# mechanics.net
KiCad netlist of a schematic drawn in Altium Designer
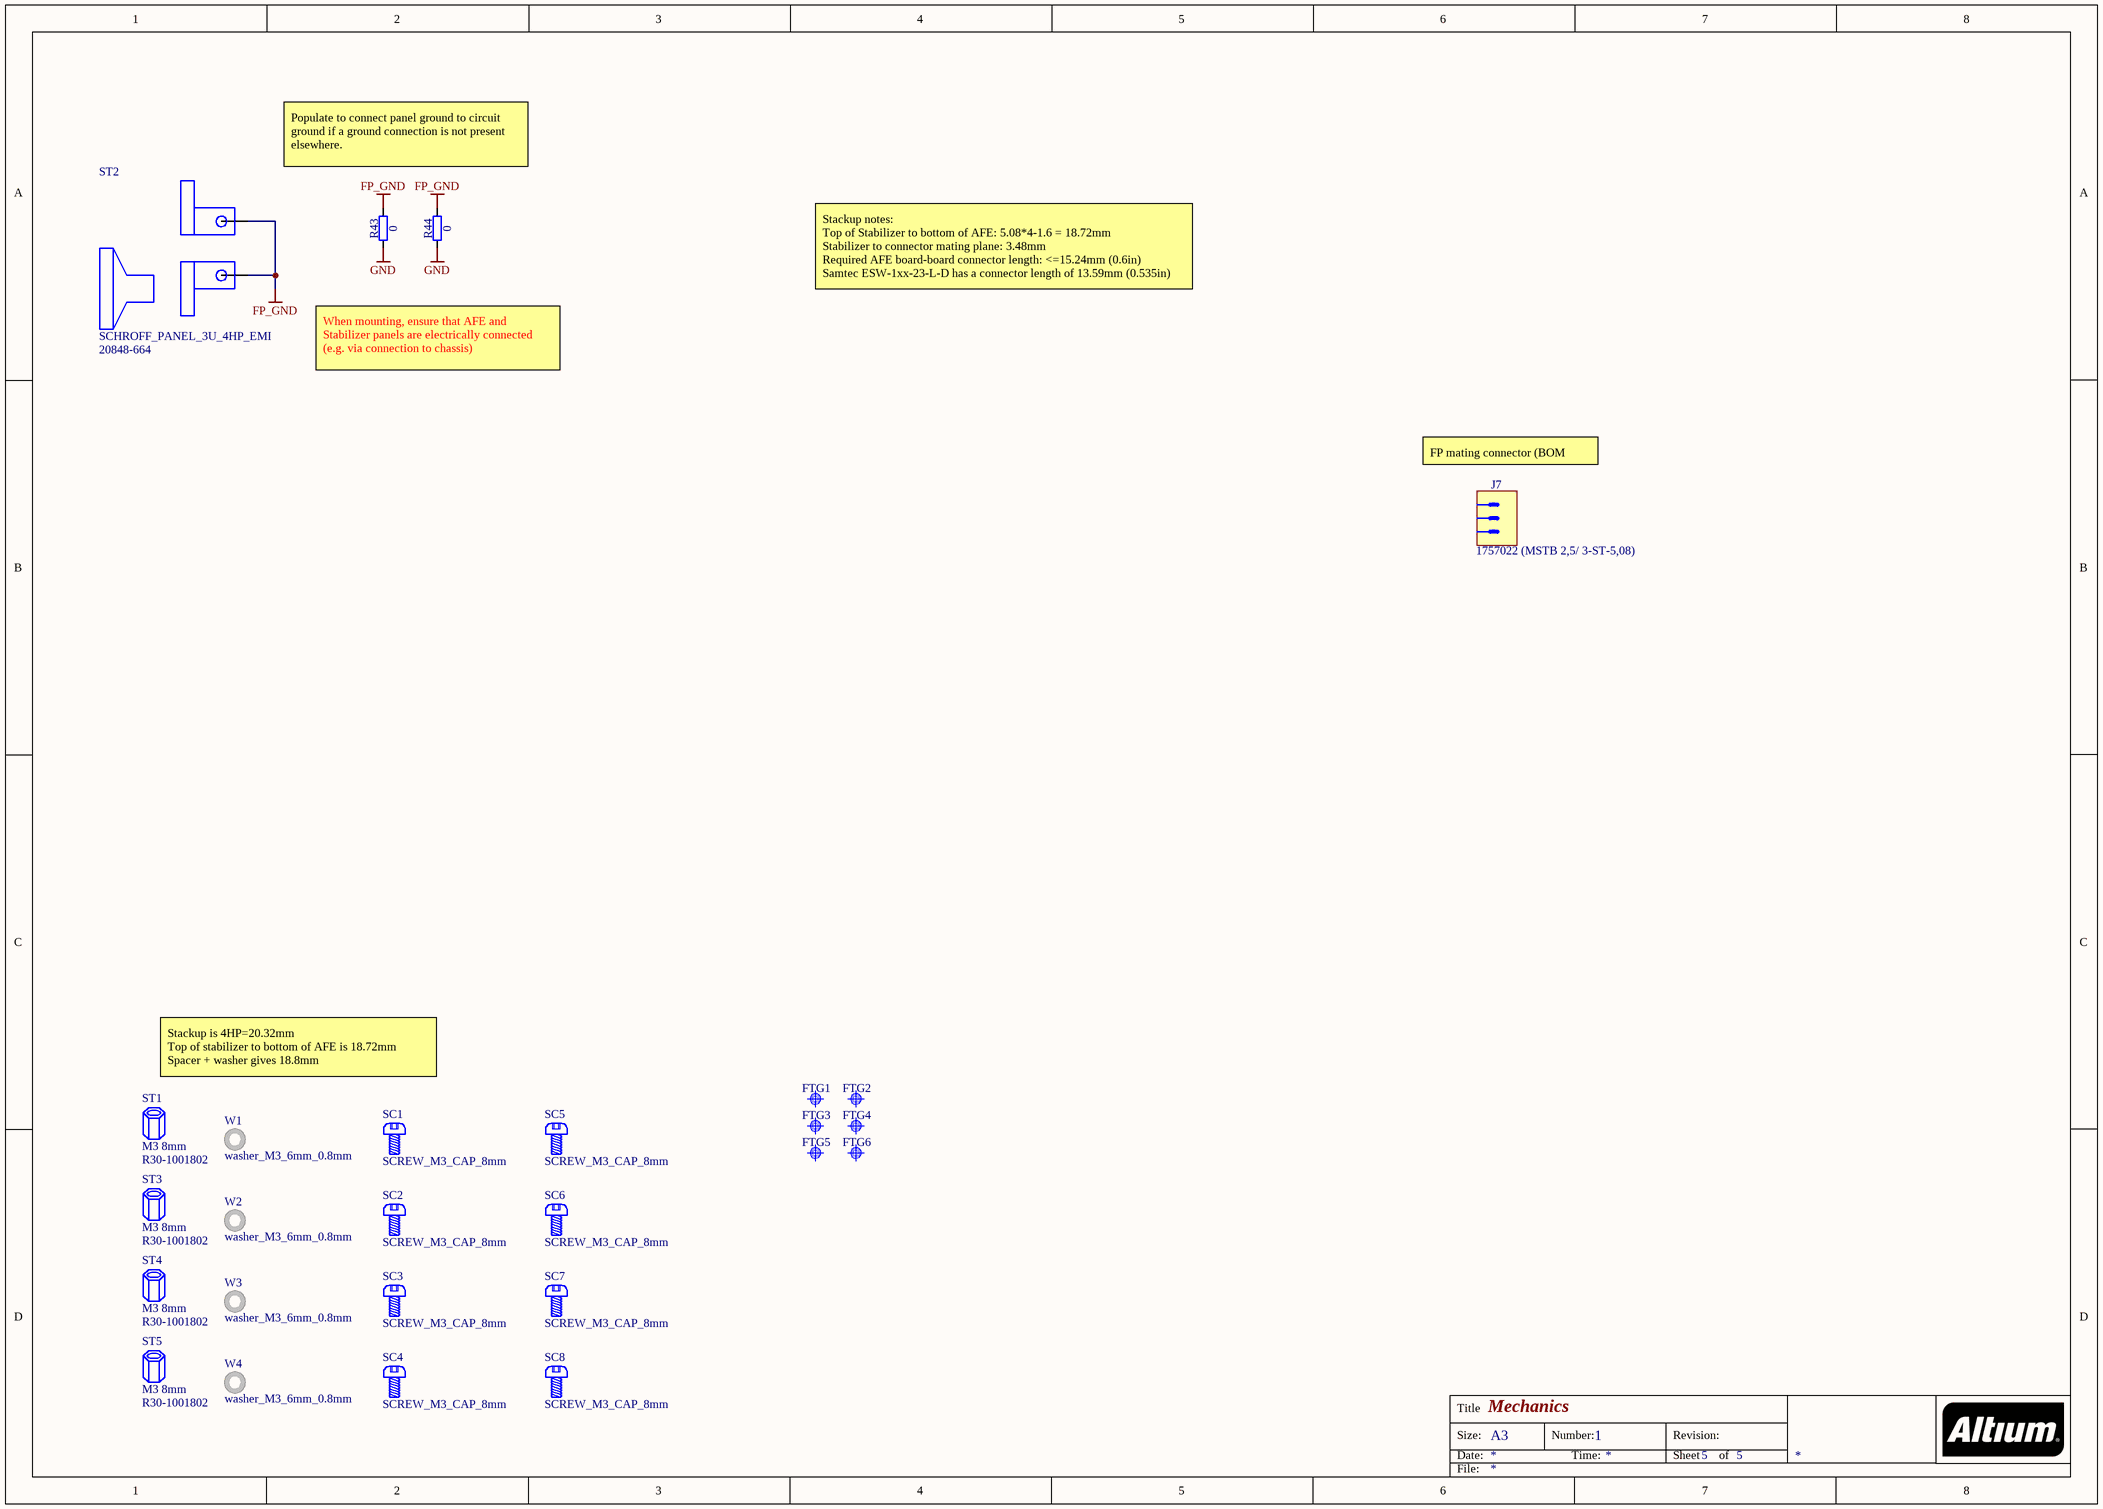
[diagram p0: mechanics.SchDoc]

(export (version "E")
  (design (tool "Eeschema 10.0.6"))
  (components
    (comp (ref "FTG1")
      (value "Use only in PCB")
      (footprint "FIDUCIAL_TOP_C100-200")
      (description "Fiducial Target")
      (fields (field (name "PART NUMBER") "FIDUCIAL_TARGET_C100-200") (field (name "AUTHOR") "CERN DEM JLC"))
      (libsource (lib "Eletro-mechanical") (part "Fiducial Target"))
    )
    (comp (ref "FTG2")
      (value "Use only in PCB")
      (footprint "FIDUCIAL_TOP_C100-200")
      (description "Fiducial Target")
      (fields (field (name "PART NUMBER") "FIDUCIAL_TARGET_C100-200") (field (name "AUTHOR") "CERN DEM JLC"))
      (libsource (lib "Eletro-mechanical") (part "Fiducial Target"))
    )
    (comp (ref "FTG3")
      (value "Use only in PCB")
      (footprint "FIDUCIAL_TOP_C100-200")
      (description "Fiducial Target")
      (fields (field (name "PART NUMBER") "FIDUCIAL_TARGET_C100-200") (field (name "AUTHOR") "CERN DEM JLC"))
      (libsource (lib "Eletro-mechanical") (part "Fiducial Target"))
    )
    (comp (ref "FTG4")
      (value "Use only in PCB")
      (footprint "FIDUCIAL_TOP_C100-200")
      (description "Fiducial Target")
      (fields (field (name "PART NUMBER") "FIDUCIAL_TARGET_C100-200") (field (name "AUTHOR") "CERN DEM JLC"))
      (libsource (lib "Eletro-mechanical") (part "Fiducial Target"))
    )
    (comp (ref "FTG5")
      (value "Use only in PCB")
      (footprint "FIDUCIAL_TOP_C100-200")
      (description "Fiducial Target")
      (fields (field (name "PART NUMBER") "FIDUCIAL_TARGET_C100-200") (field (name "AUTHOR") "CERN DEM JLC"))
      (libsource (lib "Eletro-mechanical") (part "Fiducial Target"))
    )
    (comp (ref "FTG6")
      (value "Use only in PCB")
      (footprint "FIDUCIAL_TOP_C100-200")
      (description "Fiducial Target")
      (fields (field (name "PART NUMBER") "FIDUCIAL_TARGET_C100-200") (field (name "AUTHOR") "CERN DEM JLC"))
      (libsource (lib "Eletro-mechanical") (part "Fiducial Target"))
    )
    (comp (ref "J7")
      (value "~")
      (footprint "connectors:PHOENIX_1757022")
      (description "Phoenix Contact 5.08mm pitch terminal plug, 3 ways")
      (fields
        (field (name "MANUFACTURER") "Phoenix Contact")
        (field (name "MANUFACTURER PART NUMBER") "1757022 (MSTB 2,5/ 3-ST-5,08)")
      )
      (libsource (lib "connectors") (part "PHOENIX_1757022"))
    )
    (comp (ref "R43")
      (value "0")
      (footprint "RESC1608X55N")
      (description "Resistor")
      (fields
        (field (name "PART NUMBER") "R0603_0R_JUMPER")
        (field (name "MANUFACTURER") "GENERIC")
        (field (name "AUTHOR") "CERN DEM JLC")
      )
      (libsource (lib "Resistors") (part "Resistor"))
    )
    (comp (ref "R44")
      (value "0")
      (footprint "RESC1608X55N")
      (description "Resistor")
      (fields
        (field (name "PART NUMBER") "R0603_0R_JUMPER")
        (field (name "MANUFACTURER") "GENERIC")
        (field (name "AUTHOR") "CERN DEM JLC")
      )
      (libsource (lib "Resistors") (part "Resistor"))
    )
    (comp (ref "SC1")
      (value "SCREW_M3_CAP_8mm")
      (footprint "mechanical:SCREW_M3_CAP_8mm")
      (description "M3 x 8mm cap head screw")
      (fields
        (field (name "MANUFACTURER") "Accu Limited")
        (field (name "MANUFACTURER PART NUMBER") "SSCF-M3-8-12.9-Z")
      )
      (libsource (lib "mechanical") (part "SCREW_M3_CAP_8mm"))
    )
    (comp (ref "SC2")
      (value "SCREW_M3_CAP_8mm")
      (footprint "mechanical:SCREW_M3_CAP_8mm")
      (description "M3 x 8mm cap head screw")
      (fields
        (field (name "MANUFACTURER") "Accu Limited")
        (field (name "MANUFACTURER PART NUMBER") "SSCF-M3-8-12.9-Z")
      )
      (libsource (lib "mechanical") (part "SCREW_M3_CAP_8mm"))
    )
    (comp (ref "SC3")
      (value "SCREW_M3_CAP_8mm")
      (footprint "mechanical:SCREW_M3_CAP_8mm")
      (description "M3 x 8mm cap head screw")
      (fields
        (field (name "MANUFACTURER") "Accu Limited")
        (field (name "MANUFACTURER PART NUMBER") "SSCF-M3-8-12.9-Z")
      )
      (libsource (lib "mechanical") (part "SCREW_M3_CAP_8mm"))
    )
    (comp (ref "SC4")
      (value "SCREW_M3_CAP_8mm")
      (footprint "mechanical:SCREW_M3_CAP_8mm")
      (description "M3 x 8mm cap head screw")
      (fields
        (field (name "MANUFACTURER") "Accu Limited")
        (field (name "MANUFACTURER PART NUMBER") "SSCF-M3-8-12.9-Z")
      )
      (libsource (lib "mechanical") (part "SCREW_M3_CAP_8mm"))
    )
    (comp (ref "SC5")
      (value "SCREW_M3_CAP_8mm")
      (footprint "mechanical:SCREW_M3_CAP_8mm")
      (description "M3 x 8mm cap head screw")
      (fields
        (field (name "MANUFACTURER") "Accu Limited")
        (field (name "MANUFACTURER PART NUMBER") "SSCF-M3-8-12.9-Z")
      )
      (libsource (lib "mechanical") (part "SCREW_M3_CAP_8mm"))
    )
    (comp (ref "SC6")
      (value "SCREW_M3_CAP_8mm")
      (footprint "mechanical:SCREW_M3_CAP_8mm")
      (description "M3 x 8mm cap head screw")
      (fields
        (field (name "MANUFACTURER") "Accu Limited")
        (field (name "MANUFACTURER PART NUMBER") "SSCF-M3-8-12.9-Z")
      )
      (libsource (lib "mechanical") (part "SCREW_M3_CAP_8mm"))
    )
    (comp (ref "SC7")
      (value "SCREW_M3_CAP_8mm")
      (footprint "mechanical:SCREW_M3_CAP_8mm")
      (description "M3 x 8mm cap head screw")
      (fields
        (field (name "MANUFACTURER") "Accu Limited")
        (field (name "MANUFACTURER PART NUMBER") "SSCF-M3-8-12.9-Z")
      )
      (libsource (lib "mechanical") (part "SCREW_M3_CAP_8mm"))
    )
    (comp (ref "SC8")
      (value "SCREW_M3_CAP_8mm")
      (footprint "mechanical:SCREW_M3_CAP_8mm")
      (description "M3 x 8mm cap head screw")
      (fields
        (field (name "MANUFACTURER") "Accu Limited")
        (field (name "MANUFACTURER PART NUMBER") "SSCF-M3-8-12.9-Z")
      )
      (libsource (lib "mechanical") (part "SCREW_M3_CAP_8mm"))
    )
    (comp (ref "ST1")
      (value "M3 8mm")
      (footprint "mechanical:R30-1001802")
      (description "M3.0x18 standoff")
      (fields (field (name "MANUFACTURER") "Harwin") (field (name "MANUFACTURER PART NUMBER") "R30-1001802"))
      (libsource (lib "mechanical") (part "STANDOFF_HARWIN_R30_1001802"))
    )
    (comp (ref "ST2")
      (value "SCHROFF_PANEL_3U_4HP_EMI")
      (footprint "mechanical:SCHROFF_PANEL_3HP_4U")
      (description "Schroff 3HP 4U EUROCARD Panel with EMI gaskets kit")
      (fields (field (name "MANUFACTURER") "Schroff") (field (name "MANUFACTURER PART NUMBER") "20848-664"))
      (libsource (lib "mechanical") (part "SCHROFF_PANEL_3U_4HP_EMI"))
    )
    (comp (ref "ST3")
      (value "M3 8mm")
      (footprint "mechanical:R30-1001802")
      (description "M3.0x18 standoff")
      (fields (field (name "MANUFACTURER") "Harwin") (field (name "MANUFACTURER PART NUMBER") "R30-1001802"))
      (libsource (lib "mechanical") (part "STANDOFF_HARWIN_R30_1001802"))
    )
    (comp (ref "ST4")
      (value "M3 8mm")
      (footprint "mechanical:R30-1001802")
      (description "M3.0x18 standoff")
      (fields (field (name "MANUFACTURER") "Harwin") (field (name "MANUFACTURER PART NUMBER") "R30-1001802"))
      (libsource (lib "mechanical") (part "STANDOFF_HARWIN_R30_1001802"))
    )
    (comp (ref "ST5")
      (value "M3 8mm")
      (footprint "mechanical:R30-1001802")
      (description "M3.0x18 standoff")
      (fields (field (name "MANUFACTURER") "Harwin") (field (name "MANUFACTURER PART NUMBER") "R30-1001802"))
      (libsource (lib "mechanical") (part "STANDOFF_HARWIN_R30_1001802"))
    )
    (comp (ref "W1")
      (value "washer_M3_6mm_0.8mm")
      (footprint "mechanical:washer_M3_6mm_0.8mm")
      (description "M3 Washer:\r\nID: 3.2mm\r\nOD: 6mm\r\nThickness 0.8mm")
      (fields
        (field (name "MANUFACTURER") "Accu Limited")
        (field (name "MANUFACTURER PART NUMBER") "HAFZ-M3-A4")
      )
      (libsource (lib "mechanical") (part "washer_M3_6mm_0.8mm"))
    )
    (comp (ref "W2")
      (value "washer_M3_6mm_0.8mm")
      (footprint "mechanical:washer_M3_6mm_0.8mm")
      (description "M3 Washer:\r\nID: 3.2mm\r\nOD: 6mm\r\nThickness 0.8mm")
      (fields
        (field (name "MANUFACTURER") "Accu Limited")
        (field (name "MANUFACTURER PART NUMBER") "HAFZ-M3-A4")
      )
      (libsource (lib "mechanical") (part "washer_M3_6mm_0.8mm"))
    )
    (comp (ref "W3")
      (value "washer_M3_6mm_0.8mm")
      (footprint "mechanical:washer_M3_6mm_0.8mm")
      (description "M3 Washer:\r\nID: 3.2mm\r\nOD: 6mm\r\nThickness 0.8mm")
      (fields
        (field (name "MANUFACTURER") "Accu Limited")
        (field (name "MANUFACTURER PART NUMBER") "HAFZ-M3-A4")
      )
      (libsource (lib "mechanical") (part "washer_M3_6mm_0.8mm"))
    )
    (comp (ref "W4")
      (value "washer_M3_6mm_0.8mm")
      (footprint "mechanical:washer_M3_6mm_0.8mm")
      (description "M3 Washer:\r\nID: 3.2mm\r\nOD: 6mm\r\nThickness 0.8mm")
      (fields
        (field (name "MANUFACTURER") "Accu Limited")
        (field (name "MANUFACTURER PART NUMBER") "HAFZ-M3-A4")
      )
      (libsource (lib "mechanical") (part "washer_M3_6mm_0.8mm"))
    )
  )
  (nets
    (net (code "1") (name "FP_GND") (class "Default")
      (node (ref "R43") (pin "2") (pinfunction "2_2") (pintype "passive"))
      (node (ref "R44") (pin "2") (pinfunction "2_2") (pintype "passive"))
      (node (ref "ST2") (pin "0") (pinfunction "0_0") (pintype "passive"))
      (node (ref "ST2") (pin "1") (pinfunction "1_1") (pintype "passive"))
    )
    (net (code "2") (name "GND") (class "Default")
      (node (ref "R43") (pin "1") (pinfunction "1_1") (pintype "passive"))
      (node (ref "R44") (pin "1") (pinfunction "1_1") (pintype "passive"))
    )
  )
)
